# ctrl_out.net
KiCad netlist of a schematic drawn in EAGLE
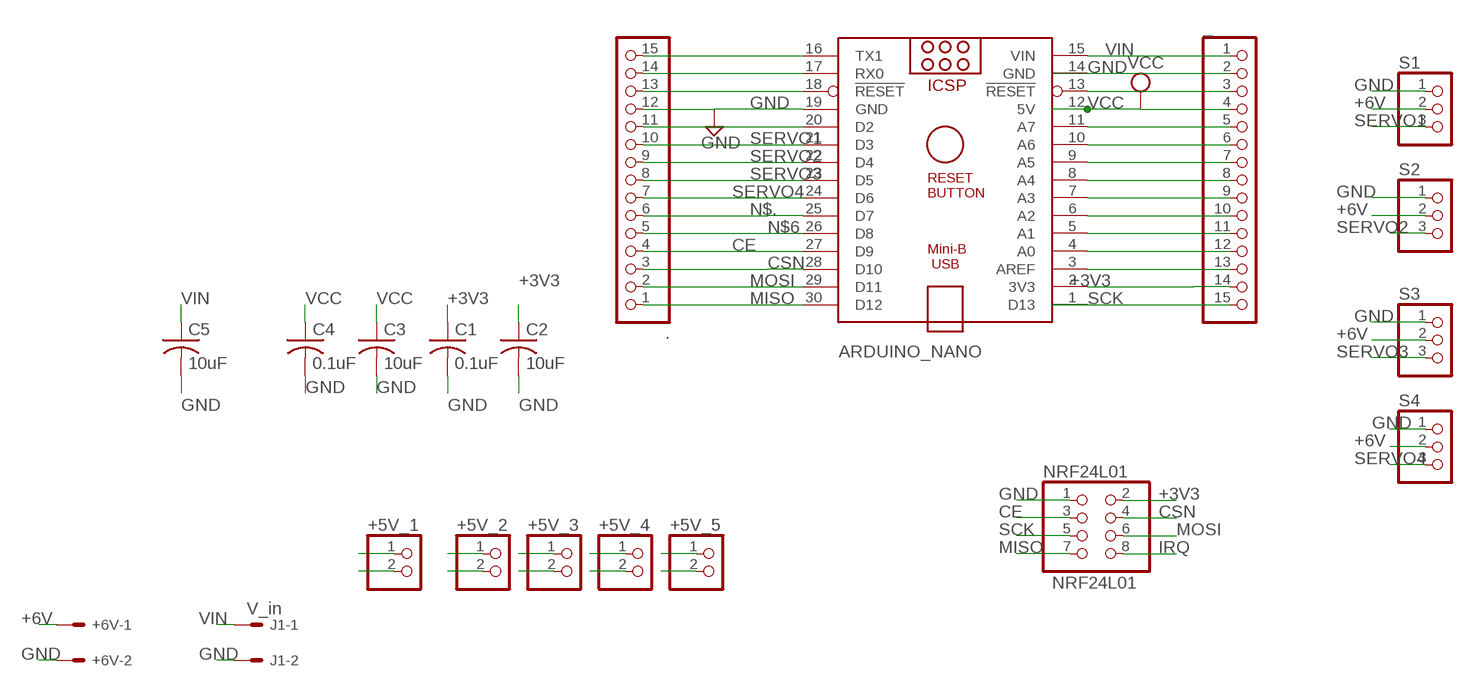
[diagram p0: schematic, sheet 1]

(export (version "E")
  (design (tool "Eeschema 10.0.6"))
  (components
    (comp (ref "+5V_1")
      (value "PINHD-1X2")
      (footprint "eagle-import:1X02")
      (libsource (lib "eagle-import") (part "PINHD-1X2"))
    )
    (comp (ref "+5V_2")
      (value "PINHD-1X2")
      (footprint "eagle-import:1X02")
      (libsource (lib "eagle-import") (part "PINHD-1X2"))
    )
    (comp (ref "+5V_3")
      (value "PINHD-1X2")
      (footprint "eagle-import:1X02")
      (libsource (lib "eagle-import") (part "PINHD-1X2"))
    )
    (comp (ref "+5V_4")
      (value "PINHD-1X2")
      (footprint "eagle-import:1X02")
      (libsource (lib "eagle-import") (part "PINHD-1X2"))
    )
    (comp (ref "+5V_5")
      (value "PINHD-1X2")
      (footprint "eagle-import:1X02")
      (libsource (lib "eagle-import") (part "PINHD-1X2"))
    )
    (comp (ref "+6V")
      (value "22-27-2021-02")
      (footprint "eagle-import:6410-02")
      (fields (field (name "MF") "MOLEX"))
      (libsource (lib "eagle-import") (part "22-?-0227-2021"))
    )
    (comp (ref ".")
      (value "PINHD-1X15")
      (footprint "eagle-import:1X15")
      (libsource (lib "eagle-import") (part "PINHD-1X15"))
    )
    (comp (ref "ARDUINO_NANO")
      (value "ARDUINO_NANO")
      (footprint "eagle-import:ARDUINO_NANO")
      (libsource (lib "eagle-import") (part "ARDUINO_NANO"))
    )
    (comp (ref "C1")
      (value "0.1uF")
      (footprint "eagle-import:C1206")
      (libsource (lib "eagle-import") (part "C-USC1206"))
    )
    (comp (ref "C2")
      (value "10uF")
      (footprint "eagle-import:C1206")
      (libsource (lib "eagle-import") (part "C-USC1206"))
    )
    (comp (ref "C3")
      (value "10uF")
      (footprint "eagle-import:C1206")
      (libsource (lib "eagle-import") (part "C-USC1206"))
    )
    (comp (ref "C4")
      (value "0.1uF")
      (footprint "eagle-import:C1206")
      (libsource (lib "eagle-import") (part "C-USC1206"))
    )
    (comp (ref "C5")
      (value "10uF")
      (footprint "eagle-import:C1206")
      (libsource (lib "eagle-import") (part "C-USC1206"))
    )
    (comp (ref "J1")
      (value "V_in")
      (footprint "eagle-import:6410-02")
      (fields (field (name "MF") "MOLEX"))
      (libsource (lib "eagle-import") (part "22-?-0227-2021"))
    )
    (comp (ref "NRF24L01")
      (value "PINHD-2X4")
      (footprint "eagle-import:2X04")
      (libsource (lib "eagle-import") (part "PINHD-2X4"))
    )
    (comp (ref "S1")
      (value "PINHD-1X3")
      (footprint "eagle-import:1X03")
      (libsource (lib "eagle-import") (part "PINHD-1X3"))
    )
    (comp (ref "S2")
      (value "PINHD-1X3")
      (footprint "eagle-import:1X03")
      (libsource (lib "eagle-import") (part "PINHD-1X3"))
    )
    (comp (ref "S3")
      (value "PINHD-1X3")
      (footprint "eagle-import:1X03")
      (libsource (lib "eagle-import") (part "PINHD-1X3"))
    )
    (comp (ref "S4")
      (value "PINHD-1X3")
      (footprint "eagle-import:1X03")
      (libsource (lib "eagle-import") (part "PINHD-1X3"))
    )
    (comp (ref "_")
      (value "PINHD-1X15")
      (footprint "eagle-import:1X15")
      (libsource (lib "eagle-import") (part "PINHD-1X15"))
    )
  )
  (nets
    (net (code "1") (name "/+3V3") (class "Default")
      (node (ref "ARDUINO_NANO") (pin "2") (pinfunction "3V3_2") (pintype "output"))
      (node (ref "C1") (pin "1") (pinfunction "1_1") (pintype "passive"))
      (node (ref "C2") (pin "1") (pinfunction "1_1") (pintype "passive"))
      (node (ref "NRF24L01") (pin "2") (pinfunction "2_2") (pintype "passive"))
      (node (ref "_") (pin "14") (pinfunction "14_14") (pintype "passive"))
    )
    (net (code "2") (name "/+6V") (class "Default")
      (node (ref "+6V") (pin "1") (pinfunction "S_1") (pintype "passive"))
      (node (ref "S1") (pin "2") (pinfunction "2_2") (pintype "passive"))
      (node (ref "S2") (pin "2") (pinfunction "2_2") (pintype "passive"))
      (node (ref "S3") (pin "2") (pinfunction "2_2") (pintype "passive"))
      (node (ref "S4") (pin "2") (pinfunction "2_2") (pintype "passive"))
    )
    (net (code "3") (name "/CE") (class "Default")
      (node (ref ".") (pin "4") (pinfunction "4_4") (pintype "passive"))
      (node (ref "ARDUINO_NANO") (pin "27") (pinfunction "D9_27") (pintype "bidirectional"))
      (node (ref "NRF24L01") (pin "3") (pinfunction "3_3") (pintype "passive"))
    )
    (net (code "4") (name "/CSN") (class "Default")
      (node (ref ".") (pin "3") (pinfunction "3_3") (pintype "passive"))
      (node (ref "ARDUINO_NANO") (pin "28") (pinfunction "D10_28") (pintype "bidirectional"))
      (node (ref "NRF24L01") (pin "4") (pinfunction "4_4") (pintype "passive"))
    )
    (net (code "5") (name "/IRQ") (class "Default")
      (node (ref "NRF24L01") (pin "8") (pinfunction "8_8") (pintype "passive"))
    )
    (net (code "6") (name "/MISO") (class "Default")
      (node (ref ".") (pin "1") (pinfunction "1_1") (pintype "passive"))
      (node (ref "ARDUINO_NANO") (pin "30") (pinfunction "D12_30") (pintype "bidirectional"))
      (node (ref "NRF24L01") (pin "7") (pinfunction "7_7") (pintype "passive"))
    )
    (net (code "7") (name "/MOSI") (class "Default")
      (node (ref ".") (pin "2") (pinfunction "2_2") (pintype "passive"))
      (node (ref "ARDUINO_NANO") (pin "29") (pinfunction "D11_29") (pintype "bidirectional"))
      (node (ref "NRF24L01") (pin "6") (pinfunction "6_6") (pintype "passive"))
    )
    (net (code "8") (name "/N$.") (class "Default")
      (node (ref ".") (pin "6") (pinfunction "6_6") (pintype "passive"))
      (node (ref "ARDUINO_NANO") (pin "25") (pinfunction "D7_25") (pintype "bidirectional"))
    )
    (net (code "9") (name "/N$6") (class "Default")
      (node (ref ".") (pin "5") (pinfunction "5_5") (pintype "passive"))
      (node (ref "ARDUINO_NANO") (pin "26") (pinfunction "D8_26") (pintype "bidirectional"))
    )
    (net (code "10") (name "/SCK") (class "Default")
      (node (ref "ARDUINO_NANO") (pin "1") (pinfunction "D13_1") (pintype "bidirectional"))
      (node (ref "NRF24L01") (pin "5") (pinfunction "5_5") (pintype "passive"))
      (node (ref "_") (pin "15") (pinfunction "15_15") (pintype "passive"))
    )
    (net (code "11") (name "/SERVO1") (class "Default")
      (node (ref ".") (pin "10") (pinfunction "10_10") (pintype "passive"))
      (node (ref "ARDUINO_NANO") (pin "21") (pinfunction "D3_21") (pintype "bidirectional"))
      (node (ref "S1") (pin "3") (pinfunction "3_3") (pintype "passive"))
    )
    (net (code "12") (name "/SERVO2") (class "Default")
      (node (ref ".") (pin "9") (pinfunction "9_9") (pintype "passive"))
      (node (ref "ARDUINO_NANO") (pin "22") (pinfunction "D4_22") (pintype "bidirectional"))
      (node (ref "S2") (pin "3") (pinfunction "3_3") (pintype "passive"))
    )
    (net (code "13") (name "/SERVO3") (class "Default")
      (node (ref ".") (pin "8") (pinfunction "8_8") (pintype "passive"))
      (node (ref "ARDUINO_NANO") (pin "23") (pinfunction "D5_23") (pintype "bidirectional"))
      (node (ref "S3") (pin "3") (pinfunction "3_3") (pintype "passive"))
    )
    (net (code "14") (name "/SERVO4") (class "Default")
      (node (ref ".") (pin "7") (pinfunction "7_7") (pintype "passive"))
      (node (ref "ARDUINO_NANO") (pin "24") (pinfunction "D6_24") (pintype "bidirectional"))
      (node (ref "S4") (pin "3") (pinfunction "3_3") (pintype "passive"))
    )
    (net (code "15") (name "/VIN") (class "Default")
      (node (ref "ARDUINO_NANO") (pin "15") (pinfunction "VIN_15") (pintype "power_in"))
      (node (ref "C5") (pin "1") (pinfunction "1_1") (pintype "passive"))
      (node (ref "J1") (pin "1") (pinfunction "S_1") (pintype "passive"))
      (node (ref "_") (pin "1") (pinfunction "1_1") (pintype "passive"))
    )
    (net (code "16") (name "GND") (class "Default")
      (node (ref "+5V_1") (pin "2") (pinfunction "2_2") (pintype "passive"))
      (node (ref "+5V_2") (pin "2") (pinfunction "2_2") (pintype "passive"))
      (node (ref "+5V_3") (pin "2") (pinfunction "2_2") (pintype "passive"))
      (node (ref "+5V_4") (pin "2") (pinfunction "2_2") (pintype "passive"))
      (node (ref "+5V_5") (pin "2") (pinfunction "2_2") (pintype "passive"))
      (node (ref "+6V") (pin "2") (pinfunction "S_2") (pintype "passive"))
      (node (ref ".") (pin "12") (pinfunction "12_12") (pintype "passive"))
      (node (ref "ARDUINO_NANO") (pin "14") (pinfunction "GND_14") (pintype "power_in"))
      (node (ref "ARDUINO_NANO") (pin "19") (pinfunction "GND_19") (pintype "power_in"))
      (node (ref "C1") (pin "2") (pinfunction "2_2") (pintype "passive"))
      (node (ref "C2") (pin "2") (pinfunction "2_2") (pintype "passive"))
      (node (ref "C3") (pin "2") (pinfunction "2_2") (pintype "passive"))
      (node (ref "C4") (pin "2") (pinfunction "2_2") (pintype "passive"))
      (node (ref "C5") (pin "2") (pinfunction "2_2") (pintype "passive"))
      (node (ref "J1") (pin "2") (pinfunction "S_2") (pintype "passive"))
      (node (ref "NRF24L01") (pin "1") (pinfunction "1_1") (pintype "passive"))
      (node (ref "S1") (pin "1") (pinfunction "1_1") (pintype "passive"))
      (node (ref "S2") (pin "1") (pinfunction "1_1") (pintype "passive"))
      (node (ref "S3") (pin "1") (pinfunction "1_1") (pintype "passive"))
      (node (ref "S4") (pin "1") (pinfunction "1_1") (pintype "passive"))
      (node (ref "_") (pin "2") (pinfunction "2_2") (pintype "passive"))
    )
    (net (code "17") (name "Net-(.-Pad13)") (class "Default")
      (node (ref ".") (pin "13") (pinfunction "13_13") (pintype "passive"))
      (node (ref "ARDUINO_NANO") (pin "18") (pinfunction "~{RESET}_18") (pintype "input"))
    )
    (net (code "18") (name "Net-(ARDUINO_NANO-A0)") (class "Default")
      (node (ref "ARDUINO_NANO") (pin "4") (pinfunction "A0_4") (pintype "bidirectional"))
      (node (ref "_") (pin "12") (pinfunction "12_12") (pintype "passive"))
    )
    (net (code "19") (name "Net-(ARDUINO_NANO-A1)") (class "Default")
      (node (ref "ARDUINO_NANO") (pin "5") (pinfunction "A1_5") (pintype "bidirectional"))
      (node (ref "_") (pin "11") (pinfunction "11_11") (pintype "passive"))
    )
    (net (code "20") (name "Net-(ARDUINO_NANO-A2)") (class "Default")
      (node (ref "ARDUINO_NANO") (pin "6") (pinfunction "A2_6") (pintype "bidirectional"))
      (node (ref "_") (pin "10") (pinfunction "10_10") (pintype "passive"))
    )
    (net (code "21") (name "Net-(ARDUINO_NANO-A3)") (class "Default")
      (node (ref "ARDUINO_NANO") (pin "7") (pinfunction "A3_7") (pintype "bidirectional"))
      (node (ref "_") (pin "9") (pinfunction "9_9") (pintype "passive"))
    )
    (net (code "22") (name "Net-(ARDUINO_NANO-A4)") (class "Default")
      (node (ref "ARDUINO_NANO") (pin "8") (pinfunction "A4_8") (pintype "bidirectional"))
      (node (ref "_") (pin "8") (pinfunction "8_8") (pintype "passive"))
    )
    (net (code "23") (name "Net-(ARDUINO_NANO-A5)") (class "Default")
      (node (ref "ARDUINO_NANO") (pin "9") (pinfunction "A5_9") (pintype "bidirectional"))
      (node (ref "_") (pin "7") (pinfunction "7_7") (pintype "passive"))
    )
    (net (code "24") (name "Net-(ARDUINO_NANO-A6)") (class "Default")
      (node (ref "ARDUINO_NANO") (pin "10") (pinfunction "A6_10") (pintype "bidirectional"))
      (node (ref "_") (pin "6") (pinfunction "6_6") (pintype "passive"))
    )
    (net (code "25") (name "Net-(ARDUINO_NANO-A7)") (class "Default")
      (node (ref "ARDUINO_NANO") (pin "11") (pinfunction "A7_11") (pintype "bidirectional"))
      (node (ref "_") (pin "5") (pinfunction "5_5") (pintype "passive"))
    )
    (net (code "26") (name "Net-(ARDUINO_NANO-AREF)") (class "Default")
      (node (ref "ARDUINO_NANO") (pin "3") (pinfunction "AREF_3") (pintype "input"))
      (node (ref "_") (pin "13") (pinfunction "13_13") (pintype "passive"))
    )
    (net (code "27") (name "Net-(ARDUINO_NANO-D2)") (class "Default")
      (node (ref ".") (pin "11") (pinfunction "11_11") (pintype "passive"))
      (node (ref "ARDUINO_NANO") (pin "20") (pinfunction "D2_20") (pintype "bidirectional"))
    )
    (net (code "28") (name "Net-(ARDUINO_NANO-RX0)") (class "Default")
      (node (ref ".") (pin "14") (pinfunction "14_14") (pintype "passive"))
      (node (ref "ARDUINO_NANO") (pin "17") (pinfunction "RX0_17") (pintype "bidirectional"))
    )
    (net (code "29") (name "Net-(ARDUINO_NANO-TX1)") (class "Default")
      (node (ref ".") (pin "15") (pinfunction "15_15") (pintype "passive"))
      (node (ref "ARDUINO_NANO") (pin "16") (pinfunction "TX1_16") (pintype "bidirectional"))
    )
    (net (code "30") (name "Net-(ARDUINO_NANO-~{RESET}-Pad13)") (class "Default")
      (node (ref "ARDUINO_NANO") (pin "13") (pinfunction "~{RESET}_13") (pintype "input"))
      (node (ref "_") (pin "3") (pinfunction "3_3") (pintype "passive"))
    )
    (net (code "31") (name "VCC") (class "Default")
      (node (ref "+5V_1") (pin "1") (pinfunction "1_1") (pintype "passive"))
      (node (ref "+5V_2") (pin "1") (pinfunction "1_1") (pintype "passive"))
      (node (ref "+5V_3") (pin "1") (pinfunction "1_1") (pintype "passive"))
      (node (ref "+5V_4") (pin "1") (pinfunction "1_1") (pintype "passive"))
      (node (ref "+5V_5") (pin "1") (pinfunction "1_1") (pintype "passive"))
      (node (ref "ARDUINO_NANO") (pin "12") (pinfunction "5V_12") (pintype "power_in"))
      (node (ref "C3") (pin "1") (pinfunction "1_1") (pintype "passive"))
      (node (ref "C4") (pin "1") (pinfunction "1_1") (pintype "passive"))
      (node (ref "_") (pin "4") (pinfunction "4_4") (pintype "passive"))
    )
  )
)
